# stepper_fw_bw_w_input_control.net
KiCad netlist of a schematic drawn in EAGLE
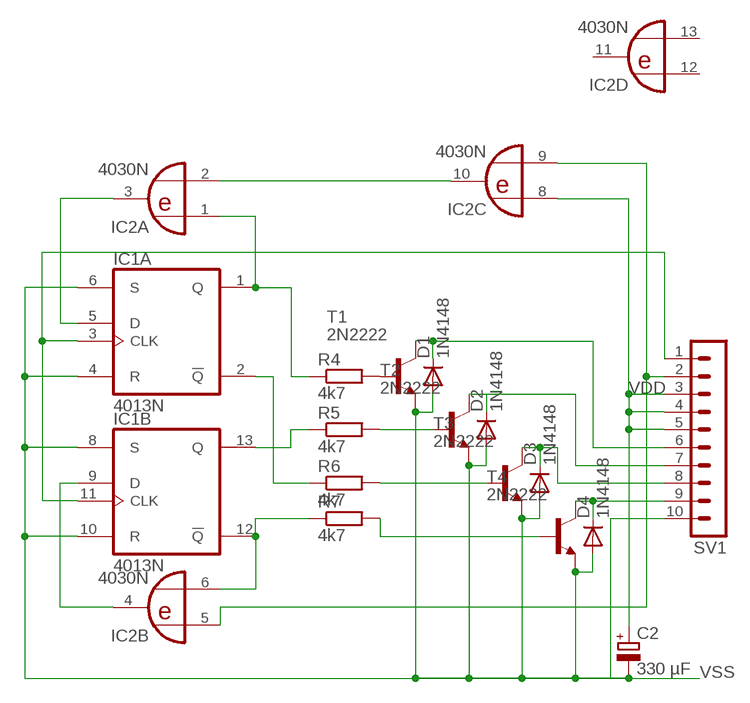
[diagram p0: schematic, sheet 1]

(export (version "E")
  (design (tool "Eeschema 10.0.6"))
  (components
    (comp (ref "C2")
      (value "330 µF")
      (footprint "eagle-import:E2,5-5")
      (libsource (lib "eagle-import") (part "CPOL-EUE2.5-5"))
    )
    (comp (ref "D1")
      (value "1N4148")
      (footprint "eagle-import:D-2.5")
      (libsource (lib "eagle-import") (part "DIODE-D-2.5"))
    )
    (comp (ref "D2")
      (value "1N4148")
      (footprint "eagle-import:D-2.5")
      (libsource (lib "eagle-import") (part "DIODE-D-2.5"))
    )
    (comp (ref "D3")
      (value "1N4148")
      (footprint "eagle-import:D-2.5")
      (libsource (lib "eagle-import") (part "DIODE-D-2.5"))
    )
    (comp (ref "D4")
      (value "1N4148")
      (footprint "eagle-import:D-2.5")
      (libsource (lib "eagle-import") (part "DIODE-D-2.5"))
    )
    (comp (ref "IC1")
      (value "4013N")
      (footprint "eagle-import:DIL14")
      (libsource (lib "eagle-import") (part "4013N"))
    )
    (comp (ref "IC2")
      (value "4030N")
      (footprint "eagle-import:DIL14")
      (libsource (lib "eagle-import") (part "4030N"))
    )
    (comp (ref "R4")
      (value "4k7")
      (footprint "eagle-import:0207_10")
      (libsource (lib "eagle-import") (part "R-EU_0207/10"))
    )
    (comp (ref "R5")
      (value "4k7")
      (footprint "eagle-import:0207_10")
      (libsource (lib "eagle-import") (part "R-EU_0207/10"))
    )
    (comp (ref "R6")
      (value "4k7")
      (footprint "eagle-import:0207_10")
      (libsource (lib "eagle-import") (part "R-EU_0207/10"))
    )
    (comp (ref "R7")
      (value "4k7")
      (footprint "eagle-import:0207_10")
      (libsource (lib "eagle-import") (part "R-EU_0207/10"))
    )
    (comp (ref "SV1")
      (value "MA10-1")
      (footprint "eagle-import:MA10-1")
      (libsource (lib "eagle-import") (part "MA10-1"))
    )
    (comp (ref "T1")
      (value "2N2222")
      (footprint "eagle-import:TO18")
      (libsource (lib "eagle-import") (part "2N2222"))
    )
    (comp (ref "T2")
      (value "2N2222")
      (footprint "eagle-import:TO18")
      (libsource (lib "eagle-import") (part "2N2222"))
    )
    (comp (ref "T3")
      (value "2N2222")
      (footprint "eagle-import:TO18")
      (libsource (lib "eagle-import") (part "2N2222"))
    )
    (comp (ref "T4")
      (value "2N2222")
      (footprint "eagle-import:TO18")
      (libsource (lib "eagle-import") (part "2N2222"))
    )
  )
  (nets
    (net (code "1") (name "/VDD") (class "Default")
      (node (ref "C2") (pin "+") (pinfunction "+_+") (pintype "passive"))
      (node (ref "IC2") (pin "8") (pinfunction "I0_8") (pintype "input"))
      (node (ref "SV1") (pin "3") (pinfunction "3_3") (pintype "passive"))
      (node (ref "SV1") (pin "4") (pinfunction "4_4") (pintype "passive"))
      (node (ref "SV1") (pin "5") (pinfunction "5_5") (pintype "passive"))
    )
    (net (code "2") (name "/VSS") (class "Default")
      (node (ref "C2") (pin "-") (pinfunction "-_-") (pintype "passive"))
      (node (ref "D1") (pin "A") (pinfunction "A_A") (pintype "passive"))
      (node (ref "D2") (pin "A") (pinfunction "A_A") (pintype "passive"))
      (node (ref "D3") (pin "A") (pinfunction "A_A") (pintype "passive"))
      (node (ref "D4") (pin "A") (pinfunction "A_A") (pintype "passive"))
      (node (ref "IC1") (pin "10") (pinfunction "R_10") (pintype "input"))
      (node (ref "IC1") (pin "4") (pinfunction "R_4") (pintype "input"))
      (node (ref "IC1") (pin "6") (pinfunction "S_6") (pintype "input"))
      (node (ref "IC1") (pin "8") (pinfunction "S_8") (pintype "input"))
      (node (ref "SV1") (pin "10") (pinfunction "10_10") (pintype "passive"))
      (node (ref "T1") (pin "1") (pinfunction "E_1") (pintype "passive"))
      (node (ref "T2") (pin "1") (pinfunction "E_1") (pintype "passive"))
      (node (ref "T3") (pin "1") (pinfunction "E_1") (pintype "passive"))
      (node (ref "T4") (pin "1") (pinfunction "E_1") (pintype "passive"))
    )
    (net (code "3") (name "Net-(IC1A-CLK)") (class "Default")
      (node (ref "IC1") (pin "11") (pinfunction "CLK_11") (pintype "input"))
      (node (ref "IC1") (pin "3") (pinfunction "CLK_3") (pintype "input"))
      (node (ref "SV1") (pin "1") (pinfunction "1_1") (pintype "passive"))
    )
    (net (code "4") (name "Net-(IC1A-D)") (class "Default")
      (node (ref "IC1") (pin "5") (pinfunction "D_5") (pintype "input"))
      (node (ref "IC2") (pin "3") (pinfunction "O_3") (pintype "output"))
    )
    (net (code "5") (name "Net-(IC1A-Q)") (class "Default")
      (node (ref "IC1") (pin "1") (pinfunction "Q_1") (pintype "output"))
      (node (ref "IC2") (pin "1") (pinfunction "I0_1") (pintype "input"))
      (node (ref "R4") (pin "1") (pinfunction "1_1") (pintype "passive"))
    )
    (net (code "6") (name "Net-(IC1A-~{Q})") (class "Default")
      (node (ref "IC1") (pin "2") (pinfunction "~{Q}_2") (pintype "output"))
      (node (ref "R6") (pin "1") (pinfunction "1_1") (pintype "passive"))
    )
    (net (code "7") (name "Net-(IC1B-D)") (class "Default")
      (node (ref "IC1") (pin "9") (pinfunction "D_9") (pintype "input"))
      (node (ref "IC2") (pin "4") (pinfunction "O_4") (pintype "output"))
    )
    (net (code "8") (name "Net-(IC1B-Q)") (class "Default")
      (node (ref "IC1") (pin "13") (pinfunction "Q_13") (pintype "output"))
      (node (ref "R5") (pin "1") (pinfunction "1_1") (pintype "passive"))
    )
    (net (code "9") (name "Net-(IC1B-~{Q})") (class "Default")
      (node (ref "IC1") (pin "12") (pinfunction "~{Q}_12") (pintype "output"))
      (node (ref "IC2") (pin "6") (pinfunction "I1_6") (pintype "input"))
      (node (ref "R7") (pin "1") (pinfunction "1_1") (pintype "passive"))
    )
    (net (code "10") (name "Net-(IC2A-I1)") (class "Default")
      (node (ref "IC2") (pin "10") (pinfunction "O_10") (pintype "output"))
      (node (ref "IC2") (pin "2") (pinfunction "I1_2") (pintype "input"))
    )
    (net (code "11") (name "Net-(IC2B-I0)") (class "Default")
      (node (ref "IC2") (pin "5") (pinfunction "I0_5") (pintype "input"))
      (node (ref "IC2") (pin "9") (pinfunction "I1_9") (pintype "input"))
      (node (ref "SV1") (pin "2") (pinfunction "2_2") (pintype "passive"))
    )
    (net (code "12") (name "Net-(T1-B)") (class "Default")
      (node (ref "R4") (pin "2") (pinfunction "2_2") (pintype "passive"))
      (node (ref "T1") (pin "2") (pinfunction "B_2") (pintype "passive"))
    )
    (net (code "13") (name "Net-(T1-C)") (class "Default")
      (node (ref "D1") (pin "C") (pinfunction "C_C") (pintype "passive"))
      (node (ref "SV1") (pin "6") (pinfunction "6_6") (pintype "passive"))
      (node (ref "T1") (pin "3") (pinfunction "C_3") (pintype "passive"))
    )
    (net (code "14") (name "Net-(T2-B)") (class "Default")
      (node (ref "R5") (pin "2") (pinfunction "2_2") (pintype "passive"))
      (node (ref "T2") (pin "2") (pinfunction "B_2") (pintype "passive"))
    )
    (net (code "15") (name "Net-(T2-C)") (class "Default")
      (node (ref "D2") (pin "C") (pinfunction "C_C") (pintype "passive"))
      (node (ref "SV1") (pin "7") (pinfunction "7_7") (pintype "passive"))
      (node (ref "T2") (pin "3") (pinfunction "C_3") (pintype "passive"))
    )
    (net (code "16") (name "Net-(T3-B)") (class "Default")
      (node (ref "R6") (pin "2") (pinfunction "2_2") (pintype "passive"))
      (node (ref "T3") (pin "2") (pinfunction "B_2") (pintype "passive"))
    )
    (net (code "17") (name "Net-(T3-C)") (class "Default")
      (node (ref "D3") (pin "C") (pinfunction "C_C") (pintype "passive"))
      (node (ref "SV1") (pin "8") (pinfunction "8_8") (pintype "passive"))
      (node (ref "T3") (pin "3") (pinfunction "C_3") (pintype "passive"))
    )
    (net (code "18") (name "Net-(T4-B)") (class "Default")
      (node (ref "R7") (pin "2") (pinfunction "2_2") (pintype "passive"))
      (node (ref "T4") (pin "2") (pinfunction "B_2") (pintype "passive"))
    )
    (net (code "19") (name "Net-(T4-C)") (class "Default")
      (node (ref "D4") (pin "C") (pinfunction "C_C") (pintype "passive"))
      (node (ref "SV1") (pin "9") (pinfunction "9_9") (pintype "passive"))
      (node (ref "T4") (pin "3") (pinfunction "C_3") (pintype "passive"))
    )
    (net (code "20") (name "unconnected-(IC2D-I0-Pad12)") (class "Default")
      (node (ref "IC2") (pin "12") (pinfunction "I0_12") (pintype "input"))
    )
    (net (code "21") (name "unconnected-(IC2D-I1-Pad13)") (class "Default")
      (node (ref "IC2") (pin "13") (pinfunction "I1_13") (pintype "input"))
    )
    (net (code "22") (name "unconnected-(IC2D-O-Pad11)") (class "Default")
      (node (ref "IC2") (pin "11") (pinfunction "O_11") (pintype "output"))
    )
  )
)
